# walle.net
KiCad netlist of a schematic drawn in EAGLE
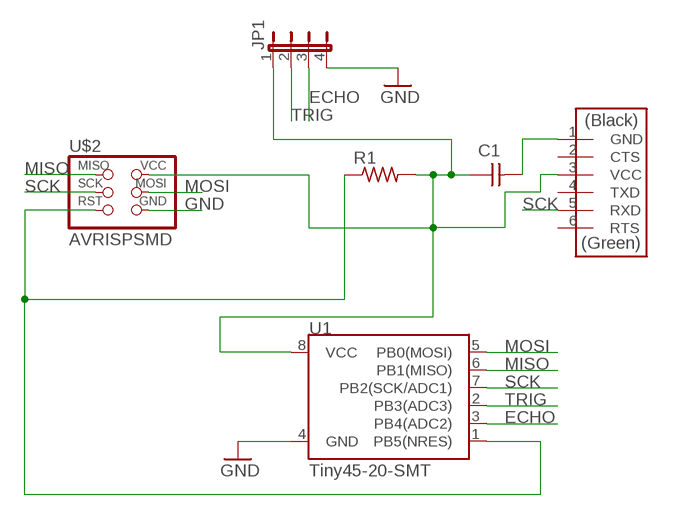
[diagram p0: schematic, sheet 1]

(export (version "E")
  (design (tool "Eeschema 10.0.6"))
  (components
    (comp (ref "C1")
      (value "CAP-UNPOLARIZED")
      (footprint "eagle-import:C1206")
      (libsource (lib "eagle-import") (part "CAP-UNPOLARIZED"))
    )
    (comp (ref "JP1")
      (value "JP4E")
      (footprint "eagle-import:JP4")
      (libsource (lib "eagle-import") (part "JP4E"))
    )
    (comp (ref "R1")
      (value "RES-US1206")
      (footprint "eagle-import:R1206")
      (libsource (lib "eagle-import") (part "RES-US1206"))
    )
    (comp (ref "U$2")
      (value "AVRISPSMD")
      (footprint "eagle-import:2X03SMD")
      (libsource (lib "eagle-import") (part "AVRISPSMD"))
    )
    (comp (ref "U$3")
      (value "FTDI-SMD-HEADER")
      (footprint "eagle-import:1X06SMD")
      (libsource (lib "eagle-import") (part "FTDI-SMD-HEADER"))
    )
    (comp (ref "U1")
      (value "Tiny45-20-SMT")
      (footprint "eagle-import:SO08-EIAJ")
      (libsource (lib "eagle-import") (part "ATTINY45TINY45-20-SMT"))
    )
  )
  (nets
    (net (code "1") (name "/ECHO") (class "Default")
      (node (ref "JP1") (pin "3") (pinfunction "3_3") (pintype "passive"))
      (node (ref "U1") (pin "3") (pinfunction "PB4(ADC2)_3") (pintype "bidirectional"))
    )
    (net (code "2") (name "/MISO") (class "Default")
      (node (ref "U$2") (pin "1") (pinfunction "MISO_1") (pintype "passive"))
      (node (ref "U1") (pin "6") (pinfunction "PB1(MISO)_6") (pintype "bidirectional"))
    )
    (net (code "3") (name "/MOSI") (class "Default")
      (node (ref "U$2") (pin "4") (pinfunction "MOSI_4") (pintype "passive"))
      (node (ref "U1") (pin "5") (pinfunction "PB0(MOSI)_5") (pintype "bidirectional"))
    )
    (net (code "4") (name "/SCK") (class "Default")
      (node (ref "U$2") (pin "3") (pinfunction "SCK_3") (pintype "passive"))
      (node (ref "U$3") (pin "5") (pinfunction "RXD_5") (pintype "bidirectional"))
      (node (ref "U1") (pin "7") (pinfunction "PB2(SCK/ADC1)_7") (pintype "bidirectional"))
    )
    (net (code "5") (name "/TRIG") (class "Default")
      (node (ref "JP1") (pin "2") (pinfunction "2_2") (pintype "passive"))
      (node (ref "U1") (pin "2") (pinfunction "PB3(ADC3)_2") (pintype "bidirectional"))
    )
    (net (code "6") (name "GND") (class "Default")
      (node (ref "JP1") (pin "4") (pinfunction "4_4") (pintype "passive"))
      (node (ref "U$2") (pin "6") (pinfunction "GND_6") (pintype "passive"))
      (node (ref "U1") (pin "4") (pinfunction "GND_4") (pintype "bidirectional"))
    )
    (net (code "7") (name "Net-(U$2-RST)") (class "Default")
      (node (ref "R1") (pin "1") (pinfunction "1_1") (pintype "passive"))
      (node (ref "U$2") (pin "5") (pinfunction "RST_5") (pintype "passive"))
      (node (ref "U1") (pin "1") (pinfunction "PB5(NRES)_1") (pintype "bidirectional"))
    )
    (net (code "8") (name "Net-(U$2-VCC)") (class "Default")
      (node (ref "C1") (pin "1") (pinfunction "1_1") (pintype "passive"))
      (node (ref "JP1") (pin "1") (pinfunction "1_1") (pintype "passive"))
      (node (ref "R1") (pin "2") (pinfunction "2_2") (pintype "passive"))
      (node (ref "U$2") (pin "2") (pinfunction "VCC_2") (pintype "passive"))
      (node (ref "U$3") (pin "3") (pinfunction "VCC_3") (pintype "bidirectional"))
      (node (ref "U1") (pin "8") (pinfunction "VCC_8") (pintype "bidirectional"))
    )
    (net (code "9") (name "Net-(U$3-GND)") (class "Default")
      (node (ref "C1") (pin "2") (pinfunction "2_2") (pintype "passive"))
      (node (ref "U$3") (pin "1") (pinfunction "GND_1") (pintype "bidirectional"))
    )
    (net (code "10") (name "unconnected-(U$3-CTS-Pad2)") (class "Default")
      (node (ref "U$3") (pin "2") (pinfunction "CTS_2") (pintype "bidirectional"))
    )
    (net (code "11") (name "unconnected-(U$3-RTS-Pad6)") (class "Default")
      (node (ref "U$3") (pin "6") (pinfunction "RTS_6") (pintype "bidirectional"))
    )
    (net (code "12") (name "unconnected-(U$3-TXD-Pad4)") (class "Default")
      (node (ref "U$3") (pin "4") (pinfunction "TXD_4") (pintype "bidirectional"))
    )
  )
)
